# AstableMultivibrator-NPN-alt.net
KiCad netlist of a schematic drawn in EAGLE
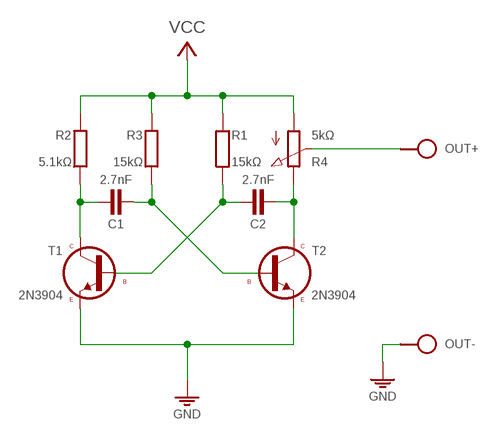
[diagram p0: schematic, sheet 1]

(export (version "E")
  (design (tool "Eeschema 10.0.6"))
  (components
    (comp (ref "C1")
      (value "2.7nF")
      (footprint "eagle-import:C0750-020X044")
      (libsource (lib "eagle-import") (part "C-H075-020X044"))
    )
    (comp (ref "C2")
      (value "2.7nF")
      (footprint "eagle-import:C0750-020X044")
      (libsource (lib "eagle-import") (part "C-H075-020X044"))
    )
    (comp (ref "J1")
      (value "VCC_GNDPWR-L")
      (footprint "eagle-import:PWR-L")
      (libsource (lib "eagle-import") (part "VCC_GNDPWR-L"))
    )
    (comp (ref "OUT")
      (value "SPAD+-+-")
      (footprint "eagle-import:SPAD+-")
      (libsource (lib "eagle-import") (part "SPAD+-+-"))
    )
    (comp (ref "R1")
      (value "15kΩ")
      (footprint "eagle-import:0204_10-V")
      (libsource (lib "eagle-import") (part "R0204/10-V"))
    )
    (comp (ref "R2")
      (value "5.1kΩ")
      (footprint "eagle-import:0204_10-V")
      (libsource (lib "eagle-import") (part "R0204/10-V"))
    )
    (comp (ref "R3")
      (value "15kΩ")
      (footprint "eagle-import:0204_10-V")
      (libsource (lib "eagle-import") (part "R0204/10-V"))
    )
    (comp (ref "R4")
      (value "5kΩ")
      (footprint "eagle-import:POT-V")
      (libsource (lib "eagle-import") (part "POT-V"))
    )
    (comp (ref "T1")
      (value "2N3904")
      (footprint "eagle-import:TO92")
      (libsource (lib "eagle-import") (part "2N3904"))
    )
    (comp (ref "T2")
      (value "2N3904")
      (footprint "eagle-import:TO92")
      (libsource (lib "eagle-import") (part "2N3904"))
    )
  )
  (nets
    (net (code "1") (name "GND") (class "Default")
      (node (ref "J1") (pin "1") (pinfunction "GND_1") (pintype "power_in"))
      (node (ref "OUT") (pin "1") (pinfunction "P$1_1") (pintype "passive"))
      (node (ref "T1") (pin "1") (pinfunction "E_1") (pintype "passive"))
      (node (ref "T2") (pin "1") (pinfunction "E_1") (pintype "passive"))
    )
    (net (code "2") (name "Net-(J1A-VCC)") (class "Default")
      (node (ref "J1") (pin "2") (pinfunction "VCC_2") (pintype "power_in"))
      (node (ref "R1") (pin "1") (pinfunction "1_1") (pintype "passive"))
      (node (ref "R2") (pin "1") (pinfunction "1_1") (pintype "passive"))
      (node (ref "R3") (pin "1") (pinfunction "1_1") (pintype "passive"))
      (node (ref "R4") (pin "A") (pinfunction "A_A") (pintype "passive"))
    )
    (net (code "3") (name "Net-(OUTA-P$1)") (class "Default")
      (node (ref "OUT") (pin "2") (pinfunction "P$1_2") (pintype "passive"))
      (node (ref "R4") (pin "S") (pinfunction "S_S") (pintype "passive"))
    )
    (net (code "4") (name "Net-(T1-B)") (class "Default")
      (node (ref "C2") (pin "1") (pinfunction "1_1") (pintype "passive"))
      (node (ref "R1") (pin "2") (pinfunction "2_2") (pintype "passive"))
      (node (ref "T1") (pin "2") (pinfunction "B_2") (pintype "passive"))
    )
    (net (code "5") (name "Net-(T1-C)") (class "Default")
      (node (ref "C1") (pin "1") (pinfunction "1_1") (pintype "passive"))
      (node (ref "R2") (pin "2") (pinfunction "2_2") (pintype "passive"))
      (node (ref "T1") (pin "3") (pinfunction "C_3") (pintype "passive"))
    )
    (net (code "6") (name "Net-(T2-B)") (class "Default")
      (node (ref "C1") (pin "2") (pinfunction "2_2") (pintype "passive"))
      (node (ref "R3") (pin "2") (pinfunction "2_2") (pintype "passive"))
      (node (ref "T2") (pin "2") (pinfunction "B_2") (pintype "passive"))
    )
    (net (code "7") (name "Net-(T2-C)") (class "Default")
      (node (ref "C2") (pin "2") (pinfunction "2_2") (pintype "passive"))
      (node (ref "R4") (pin "E") (pinfunction "E_E") (pintype "passive"))
      (node (ref "T2") (pin "3") (pinfunction "C_3") (pintype "passive"))
    )
  )
)
